# SZG-TEMPLATE-TXR.net
KiCad netlist of a schematic drawn in Altium Designer
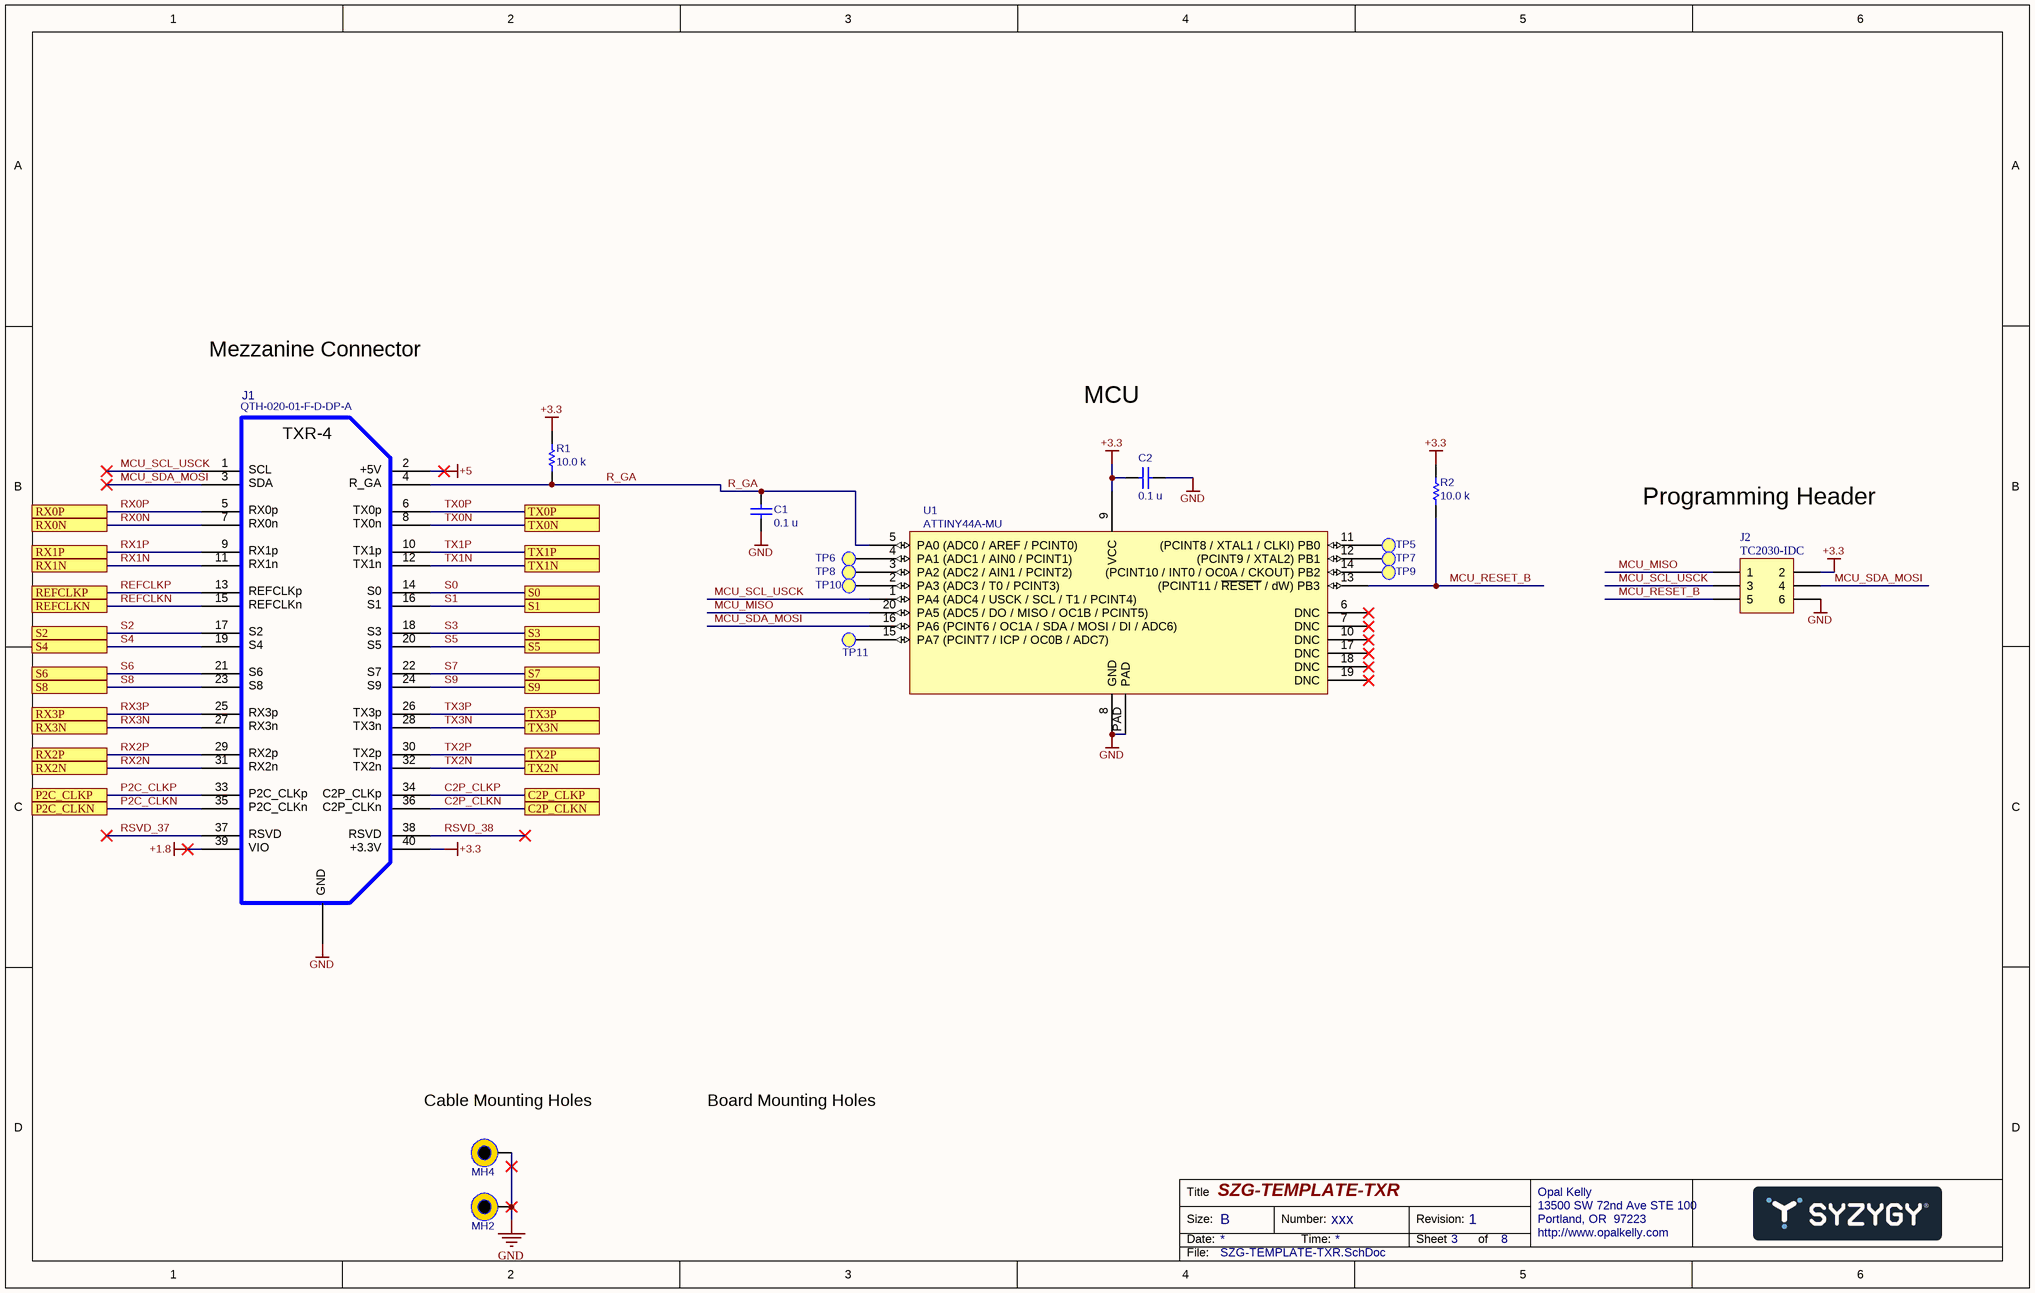
[diagram p0: SZG-TEMPLATE-TXR.SchDoc]

(export (version "E")
  (design (tool "Eeschema 10.0.6"))
  (components
    (comp (ref "C1")
      (value "0.1 u")
      (footprint "CAPC1005X06N")
      (description "Ceramic capacitor")
      (fields (field (name "MANUFACTURER") "Kemet") (field (name "PARTNUMBER") "000070"))
      (libsource (lib "Aligni") (part "Capacitor"))
    )
    (comp (ref "C2")
      (value "0.1 u")
      (footprint "CAPC1005X06N")
      (description "Ceramic capacitor")
      (fields (field (name "MANUFACTURER") "Kemet") (field (name "PARTNUMBER") "000070"))
      (libsource (lib "Aligni") (part "Capacitor"))
    )
    (comp (ref "J1")
      (value "40-pin, ground protection in middle")
      (footprint "QTH-020-01-X-D-DP-A-L")
      (description "0.5mm hi-speed, high-density header (female)")
      (fields
        (field (name "MANUFACTURER") "Samtec")
        (field (name "MANUFACTURER_PN") "QTH-020-01-F-D-DP-A")
        (field (name "ALIGNIPARTNUMBER") "001605")
      )
      (libsource (lib "Aligni") (part "QTH-DP_QSH-DP-020"))
    )
    (comp (ref "J2")
      (value "~")
      (footprint "TC2030-DUAL")
      (description "Tag-Connect 6-pin Plug-of-Nails spring-pin cable footprint")
      (fields
        (field (name "ALIGNIPARTNUMBER") "002062")
        (field (name "MANUFACTURER") "Tag-Connect")
        (field (name "MANUFACTURER_PN") "TC2030-IDC")
      )
      (libsource (lib "Aligni") (part "Header 3X2"))
    )
    (comp (ref "MH2")
      (value "MTG")
      (footprint "MTG-3.2/6.5-PTH")
      (description "Mounting hole")
      (libsource (lib "NoBOM") (part "MTG"))
    )
    (comp (ref "MH4")
      (value "MTG")
      (footprint "MTG-3.2/6.5-PTH")
      (description "Mounting hole")
      (libsource (lib "NoBOM") (part "MTG"))
    )
    (comp (ref "R1")
      (value "10.0 k")
      (footprint "RESC1005X06N")
      (description "Thick-film resistor")
      (fields (field (name "MANUFACTURER") "Vishay") (field (name "PARTNUMBER") "001521"))
      (libsource (lib "Aligni") (part "Resistor"))
    )
    (comp (ref "R2")
      (value "10.0 k")
      (footprint "RESC1005X06N")
      (description "Thick-film resistor")
      (fields (field (name "MANUFACTURER") "Vishay") (field (name "PARTNUMBER") "001521"))
      (libsource (lib "Aligni") (part "Resistor"))
    )
    (comp (ref "TP5")
      (value "TESTPOINT-SMD20")
      (footprint "TP-SMD20")
      (description "Test point, surface-mount, 20mil")
      (libsource (lib "NoBOM") (part "TESTPOINT-SMD20"))
    )
    (comp (ref "TP6")
      (value "TESTPOINT-SMD20")
      (footprint "TP-SMD20")
      (description "Test point, surface-mount, 20mil")
      (libsource (lib "NoBOM") (part "TESTPOINT-SMD20"))
    )
    (comp (ref "TP7")
      (value "TESTPOINT-SMD20")
      (footprint "TP-SMD20")
      (description "Test point, surface-mount, 20mil")
      (libsource (lib "NoBOM") (part "TESTPOINT-SMD20"))
    )
    (comp (ref "TP8")
      (value "TESTPOINT-SMD20")
      (footprint "TP-SMD20")
      (description "Test point, surface-mount, 20mil")
      (libsource (lib "NoBOM") (part "TESTPOINT-SMD20"))
    )
    (comp (ref "TP9")
      (value "TESTPOINT-SMD20")
      (footprint "TP-SMD20")
      (description "Test point, surface-mount, 20mil")
      (libsource (lib "NoBOM") (part "TESTPOINT-SMD20"))
    )
    (comp (ref "TP10")
      (value "TESTPOINT-SMD20")
      (footprint "TP-SMD20")
      (description "Test point, surface-mount, 20mil")
      (libsource (lib "NoBOM") (part "TESTPOINT-SMD20"))
    )
    (comp (ref "TP11")
      (value "TESTPOINT-SMD20")
      (footprint "TP-SMD20")
      (description "Test point, surface-mount, 20mil")
      (libsource (lib "NoBOM") (part "TESTPOINT-SMD20"))
    )
    (comp (ref "U1")
      (value "ATTINY44A-MU")
      (footprint "QFN-EP-20")
      (description "8-bit MCU, 4 KB flash, 256 bytes EEPROM")
      (fields (field (name "MANUFACTURER") "Microchip") (field (name "PARTNUMBER") "001552"))
      (libsource (lib "Aligni") (part "ATTINYx4A-MU"))
    )
  )
  (nets
    (net (code "1") (name "+1.8") (class "Default")
      (node (ref "J1") (pin "39") (pinfunction "39_39") (pintype "passive"))
    )
    (net (code "2") (name "+3.3") (class "Default")
      (node (ref "C2") (pin "2") (pinfunction "2_2") (pintype "passive"))
      (node (ref "J1") (pin "40") (pinfunction "40_40") (pintype "passive"))
      (node (ref "J2") (pin "2") (pinfunction "2_2") (pintype "passive"))
      (node (ref "R1") (pin "2") (pinfunction "2_2") (pintype "passive"))
      (node (ref "R2") (pin "2") (pinfunction "2_2") (pintype "passive"))
      (node (ref "U1") (pin "9") (pinfunction "VCC_9") (pintype "power_in"))
    )
    (net (code "3") (name "+5") (class "Default")
      (node (ref "J1") (pin "2") (pinfunction "2_2") (pintype "passive"))
    )
    (net (code "4") (name "/C2P_CLKN") (class "Default")
      (node (ref "J1") (pin "36") (pinfunction "36_36") (pintype "passive"))
    )
    (net (code "5") (name "/C2P_CLKP") (class "Default")
      (node (ref "J1") (pin "34") (pinfunction "34_34") (pintype "passive"))
    )
    (net (code "6") (name "/MCU_MISO") (class "Default")
      (node (ref "J2") (pin "1") (pinfunction "1_1") (pintype "passive"))
      (node (ref "U1") (pin "20") (pinfunction "PA5_(ADC5_/_DO_/_MISO_/_OC1B_/_PCINT5)_20") (pintype "bidirectional"))
    )
    (net (code "7") (name "/MCU_RESET_B") (class "Default")
      (node (ref "J2") (pin "5") (pinfunction "5_5") (pintype "passive"))
      (node (ref "R2") (pin "1") (pinfunction "1_1") (pintype "passive"))
      (node (ref "U1") (pin "13") (pinfunction "(PCINT11_/_~{RESET}_/_dW)_PB3_13") (pintype "bidirectional"))
    )
    (net (code "8") (name "/MCU_SCL_USCK") (class "Default")
      (node (ref "J1") (pin "1") (pinfunction "1_1") (pintype "passive"))
      (node (ref "J2") (pin "3") (pinfunction "3_3") (pintype "passive"))
      (node (ref "U1") (pin "1") (pinfunction "PA4_(ADC4_/_USCK_/_SCL_/_T1_/_PCINT4)_1") (pintype "bidirectional"))
    )
    (net (code "9") (name "/MCU_SDA_MOSI") (class "Default")
      (node (ref "J1") (pin "3") (pinfunction "3_3") (pintype "passive"))
      (node (ref "J2") (pin "4") (pinfunction "4_4") (pintype "passive"))
      (node (ref "U1") (pin "16") (pinfunction "PA6_(PCINT6_/_OC1A_/_SDA_/_MOSI_/_DI_/_ADC6)_16") (pintype "bidirectional"))
    )
    (net (code "10") (name "/P2C_CLKN") (class "Default")
      (node (ref "J1") (pin "35") (pinfunction "35_35") (pintype "passive"))
    )
    (net (code "11") (name "/P2C_CLKP") (class "Default")
      (node (ref "J1") (pin "33") (pinfunction "33_33") (pintype "passive"))
    )
    (net (code "12") (name "/REFCLKN") (class "Default")
      (node (ref "J1") (pin "15") (pinfunction "15_15") (pintype "passive"))
    )
    (net (code "13") (name "/REFCLKP") (class "Default")
      (node (ref "J1") (pin "13") (pinfunction "13_13") (pintype "passive"))
    )
    (net (code "14") (name "/RSVD_37") (class "Default")
      (node (ref "J1") (pin "37") (pinfunction "37_37") (pintype "passive+no_connect"))
    )
    (net (code "15") (name "/RSVD_38") (class "Default")
      (node (ref "J1") (pin "38") (pinfunction "38_38") (pintype "passive+no_connect"))
    )
    (net (code "16") (name "/RX0N") (class "Default")
      (node (ref "J1") (pin "7") (pinfunction "7_7") (pintype "passive"))
    )
    (net (code "17") (name "/RX0P") (class "Default")
      (node (ref "J1") (pin "5") (pinfunction "5_5") (pintype "passive"))
    )
    (net (code "18") (name "/RX1N") (class "Default")
      (node (ref "J1") (pin "11") (pinfunction "11_11") (pintype "passive"))
    )
    (net (code "19") (name "/RX1P") (class "Default")
      (node (ref "J1") (pin "9") (pinfunction "9_9") (pintype "passive"))
    )
    (net (code "20") (name "/RX2N") (class "Default")
      (node (ref "J1") (pin "31") (pinfunction "31_31") (pintype "passive"))
    )
    (net (code "21") (name "/RX2P") (class "Default")
      (node (ref "J1") (pin "29") (pinfunction "29_29") (pintype "passive"))
    )
    (net (code "22") (name "/RX3N") (class "Default")
      (node (ref "J1") (pin "27") (pinfunction "27_27") (pintype "passive"))
    )
    (net (code "23") (name "/RX3P") (class "Default")
      (node (ref "J1") (pin "25") (pinfunction "25_25") (pintype "passive"))
    )
    (net (code "24") (name "/R_GA") (class "Default")
      (node (ref "C1") (pin "2") (pinfunction "2_2") (pintype "passive"))
      (node (ref "J1") (pin "4") (pinfunction "4_4") (pintype "passive"))
      (node (ref "R1") (pin "1") (pinfunction "1_1") (pintype "passive"))
      (node (ref "U1") (pin "5") (pinfunction "PA0_(ADC0_/_AREF_/_PCINT0)_5") (pintype "bidirectional"))
    )
    (net (code "25") (name "/S0") (class "Default")
      (node (ref "J1") (pin "14") (pinfunction "14_14") (pintype "passive"))
    )
    (net (code "26") (name "/S1") (class "Default")
      (node (ref "J1") (pin "16") (pinfunction "16_16") (pintype "passive"))
    )
    (net (code "27") (name "/S2") (class "Default")
      (node (ref "J1") (pin "17") (pinfunction "17_17") (pintype "passive"))
    )
    (net (code "28") (name "/S3") (class "Default")
      (node (ref "J1") (pin "18") (pinfunction "18_18") (pintype "passive"))
    )
    (net (code "29") (name "/S4") (class "Default")
      (node (ref "J1") (pin "19") (pinfunction "19_19") (pintype "passive"))
    )
    (net (code "30") (name "/S5") (class "Default")
      (node (ref "J1") (pin "20") (pinfunction "20_20") (pintype "passive"))
    )
    (net (code "31") (name "/S6") (class "Default")
      (node (ref "J1") (pin "21") (pinfunction "21_21") (pintype "passive"))
    )
    (net (code "32") (name "/S7") (class "Default")
      (node (ref "J1") (pin "22") (pinfunction "22_22") (pintype "passive"))
    )
    (net (code "33") (name "/S8") (class "Default")
      (node (ref "J1") (pin "23") (pinfunction "23_23") (pintype "passive"))
    )
    (net (code "34") (name "/S9") (class "Default")
      (node (ref "J1") (pin "24") (pinfunction "24_24") (pintype "passive"))
    )
    (net (code "35") (name "/TX0N") (class "Default")
      (node (ref "J1") (pin "8") (pinfunction "8_8") (pintype "passive"))
    )
    (net (code "36") (name "/TX0P") (class "Default")
      (node (ref "J1") (pin "6") (pinfunction "6_6") (pintype "passive"))
    )
    (net (code "37") (name "/TX1N") (class "Default")
      (node (ref "J1") (pin "12") (pinfunction "12_12") (pintype "passive"))
    )
    (net (code "38") (name "/TX1P") (class "Default")
      (node (ref "J1") (pin "10") (pinfunction "10_10") (pintype "passive"))
    )
    (net (code "39") (name "/TX2N") (class "Default")
      (node (ref "J1") (pin "32") (pinfunction "32_32") (pintype "passive"))
    )
    (net (code "40") (name "/TX2P") (class "Default")
      (node (ref "J1") (pin "30") (pinfunction "30_30") (pintype "passive"))
    )
    (net (code "41") (name "/TX3N") (class "Default")
      (node (ref "J1") (pin "28") (pinfunction "28_28") (pintype "passive"))
    )
    (net (code "42") (name "/TX3P") (class "Default")
      (node (ref "J1") (pin "26") (pinfunction "26_26") (pintype "passive"))
    )
    (net (code "43") (name "GND") (class "Default")
      (node (ref "C1") (pin "1") (pinfunction "1_1") (pintype "passive"))
      (node (ref "C2") (pin "1") (pinfunction "1_1") (pintype "passive"))
      (node (ref "J1") (pin "0") (pinfunction "GND_0") (pintype "passive"))
      (node (ref "J2") (pin "6") (pinfunction "6_6") (pintype "passive"))
      (node (ref "MH2") (pin "1") (pinfunction "1_1") (pintype "passive"))
      (node (ref "MH4") (pin "1") (pinfunction "1_1") (pintype "passive"))
      (node (ref "U1") (pin "8") (pinfunction "GND_8") (pintype "power_in"))
      (node (ref "U1") (pin "PAD") (pinfunction "PAD_PAD") (pintype "power_in"))
    )
    (net (code "44") (name "Net-(TP5-PIN)") (class "Default")
      (node (ref "TP5") (pin "1") (pinfunction "PIN_1") (pintype "passive"))
      (node (ref "U1") (pin "11") (pinfunction "(PCINT8_/_XTAL1_/_CLKI)_PB0_11") (pintype "bidirectional"))
    )
    (net (code "45") (name "Net-(TP6-PIN)") (class "Default")
      (node (ref "TP6") (pin "1") (pinfunction "PIN_1") (pintype "passive"))
      (node (ref "U1") (pin "4") (pinfunction "PA1_(ADC1_/_AIN0_/_PCINT1)_4") (pintype "bidirectional"))
    )
    (net (code "46") (name "Net-(TP7-PIN)") (class "Default")
      (node (ref "TP7") (pin "1") (pinfunction "PIN_1") (pintype "passive"))
      (node (ref "U1") (pin "12") (pinfunction "(PCINT9_/_XTAL2)_PB1_12") (pintype "bidirectional"))
    )
    (net (code "47") (name "Net-(TP8-PIN)") (class "Default")
      (node (ref "TP8") (pin "1") (pinfunction "PIN_1") (pintype "passive"))
      (node (ref "U1") (pin "3") (pinfunction "PA2_(ADC2_/_AIN1_/_PCINT2)_3") (pintype "bidirectional"))
    )
    (net (code "48") (name "Net-(TP9-PIN)") (class "Default")
      (node (ref "TP9") (pin "1") (pinfunction "PIN_1") (pintype "passive"))
      (node (ref "U1") (pin "14") (pinfunction "(PCINT10_/_INT0_/_OC0A_/_CKOUT)_PB2_14") (pintype "bidirectional"))
    )
    (net (code "49") (name "Net-(TP10-PIN)") (class "Default")
      (node (ref "TP10") (pin "1") (pinfunction "PIN_1") (pintype "passive"))
      (node (ref "U1") (pin "2") (pinfunction "PA3_(ADC3_/_T0_/_PCINT3)_2") (pintype "bidirectional"))
    )
    (net (code "50") (name "Net-(TP11-PIN)") (class "Default")
      (node (ref "TP11") (pin "1") (pinfunction "PIN_1") (pintype "passive"))
      (node (ref "U1") (pin "15") (pinfunction "PA7_(PCINT7_/_ICP_/_OC0B_/_ADC7)_15") (pintype "bidirectional"))
    )
    (net (code "51") (name "unconnected-(U1-DNC-Pad6)") (class "Default")
      (node (ref "U1") (pin "6") (pinfunction "DNC_6") (pintype "passive+no_connect"))
    )
    (net (code "52") (name "unconnected-(U1-DNC-Pad7)") (class "Default")
      (node (ref "U1") (pin "7") (pinfunction "DNC_7") (pintype "passive+no_connect"))
    )
    (net (code "53") (name "unconnected-(U1-DNC-Pad10)") (class "Default")
      (node (ref "U1") (pin "10") (pinfunction "DNC_10") (pintype "passive+no_connect"))
    )
    (net (code "54") (name "unconnected-(U1-DNC-Pad17)") (class "Default")
      (node (ref "U1") (pin "17") (pinfunction "DNC_17") (pintype "passive+no_connect"))
    )
    (net (code "55") (name "unconnected-(U1-DNC-Pad18)") (class "Default")
      (node (ref "U1") (pin "18") (pinfunction "DNC_18") (pintype "passive+no_connect"))
    )
    (net (code "56") (name "unconnected-(U1-DNC-Pad19)") (class "Default")
      (node (ref "U1") (pin "19") (pinfunction "DNC_19") (pintype "passive+no_connect"))
    )
  )
)
